# DSI_LCD.net
KiCad netlist of a schematic drawn in Altium Designer
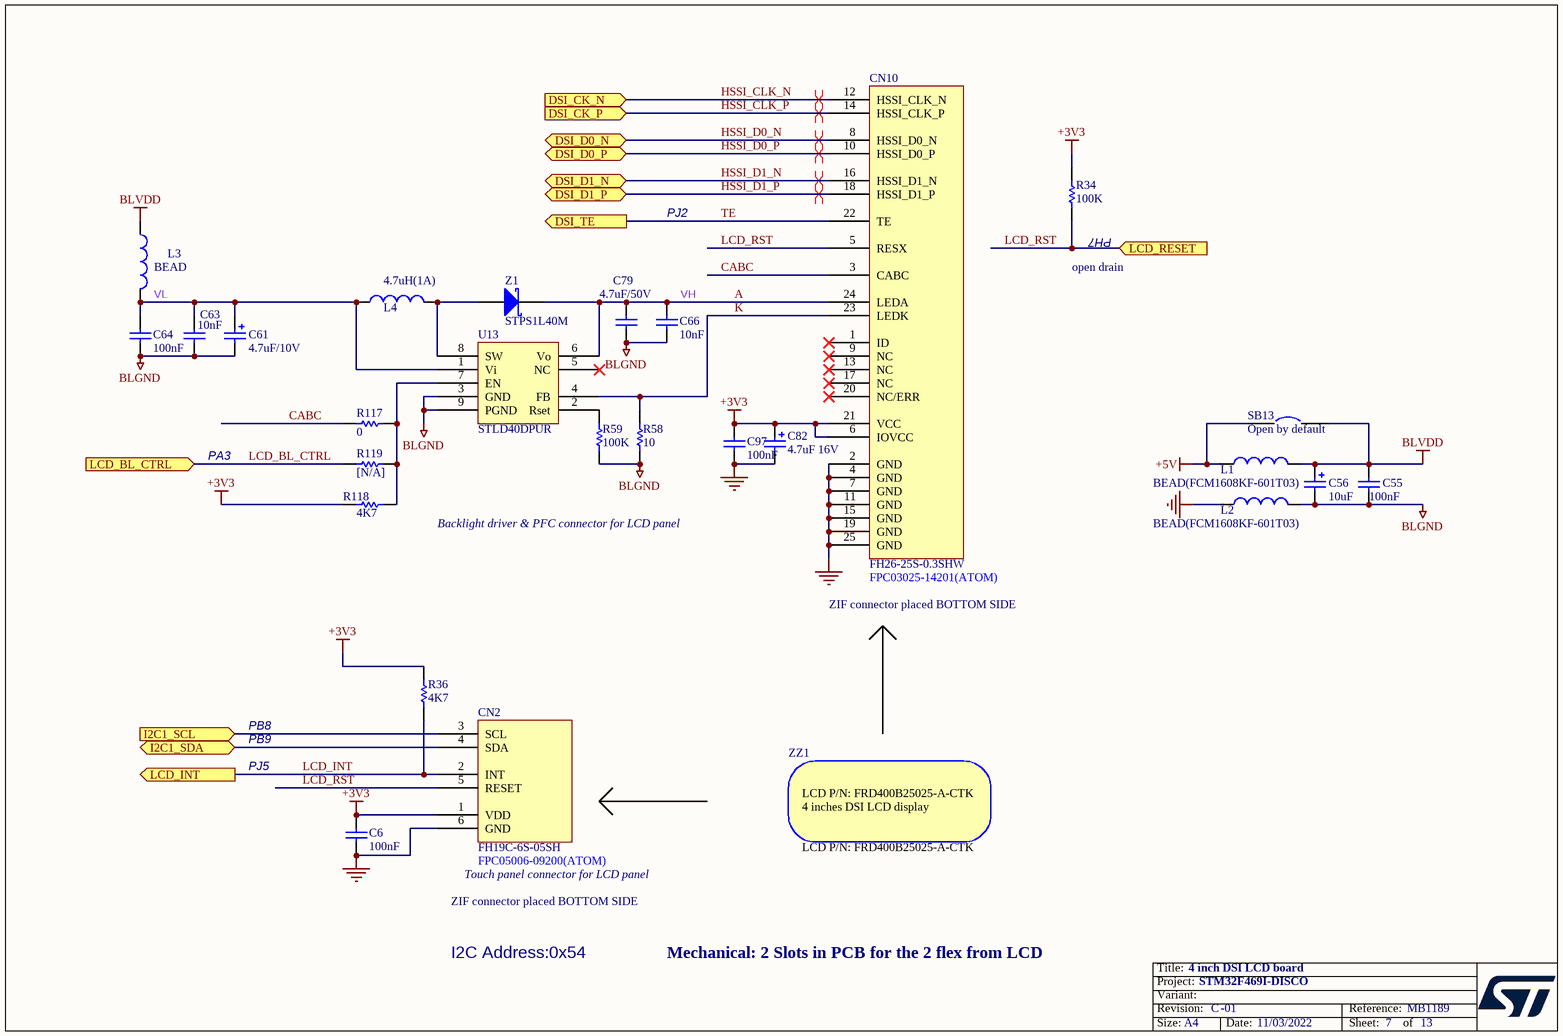
[diagram p0: DSI_LCD.SchDoc]

(export (version "E")
  (design (tool "Eeschema 10.0.6"))
  (components
    (comp (ref "C6")
      (value "100nF")
      (footprint "0402C")
      (description "Capacitor")
      (fields (field (name "PUBLISHER") "Altium Limited"))
      (libsource (lib "Miscellaneous Devices") (part "CAP"))
    )
    (comp (ref "C55")
      (value "100nF")
      (footprint "0402C")
      (description "Capacitor")
      (fields (field (name "PUBLISHER") "Altium Limited"))
      (libsource (lib "Miscellaneous Devices") (part "Cap"))
    )
    (comp (ref "C56")
      (value "10uF")
      (footprint "CPOL_TAJ-A_1206_H180")
      (description "Capacitor, Tantalum, 10uF, 16V, 10%, 3Ohms, pkg Type_A (3216 metric), T=1.6mm")
      (libsource (lib "MB1189") (part "Cap_TAJA106K016R"))
    )
    (comp (ref "C61")
      (value "4.7uF/10V")
      (footprint "1206C")
      (description "Polarized Capacitor (Radial)")
      (fields (field (name "PUBLISHER") "Altium Limited"))
      (libsource (lib "Miscellaneous Devices") (part "Cap Pol1"))
    )
    (comp (ref "C63")
      (value "10nF")
      (footprint "0603C")
      (description "Capacitor")
      (fields (field (name "PUBLISHER") "Altium Limited"))
      (libsource (lib "Miscellaneous Devices") (part "CAP"))
    )
    (comp (ref "C64")
      (value "100nF")
      (footprint "0402C")
      (description "Capacitor")
      (fields (field (name "PUBLISHER") "Altium Limited"))
      (libsource (lib "Miscellaneous Devices") (part "CAP"))
    )
    (comp (ref "C66")
      (value "10nF")
      (footprint "0603C")
      (description "Capacitor")
      (fields (field (name "PUBLISHER") "Altium Limited"))
      (libsource (lib "*") (part "CAP"))
    )
    (comp (ref "C79")
      (value "4.7uF/50V")
      (footprint "1206C")
      (description "Capacitor")
      (fields (field (name "PUBLISHER") "Altium Limited"))
      (libsource (lib "Miscellaneous Devices") (part "CAP"))
    )
    (comp (ref "C82")
      (value "4.7uF 16V")
      (footprint "CPOL_TAJ-A_1206_H180")
      (description "Capacitor, Tantalum, 4.7uF, 16V, 10%, 4ohms, pkg Type_A (3216 metric), T=1.6mm")
      (libsource (lib "MB1189") (part "Cap_TAJA475K016R"))
    )
    (comp (ref "C97")
      (value "100nF")
      (footprint "0402C")
      (description "Capacitor")
      (fields (field (name "PUBLISHER") "Altium Limited"))
      (libsource (lib "Miscellaneous Devices") (part "CAP"))
    )
    (comp (ref "CN2")
      (value "FH19C-6S-05SH")
      (footprint "FH19C-6S-0R5SH_FPC_CPT")
      (description "ZIF connector placed bottom side")
      (libsource (lib "MB1166") (part "FH19C-6S-05SH"))
    )
    (comp (ref "CN10")
      (value "FH26-25S-0.3SHW")
      (footprint "FPC25_FPC03025-1420")
      (description "ZIF connector placed bottom side")
      (libsource (lib "MB1166") (part "FH26-25S-0.3SHW"))
    )
    (comp (ref "L1")
      (value "BEAD(FCM1608KF-601T03)")
      (footprint "0603L")
      (description "Inductor")
      (fields (field (name "PUBLISHER") "Altium Limited"))
      (libsource (lib "Miscellaneous Devices") (part "Inductor"))
    )
    (comp (ref "L2")
      (value "BEAD(FCM1608KF-601T03)")
      (footprint "0603L")
      (description "Inductor")
      (fields (field (name "PUBLISHER") "Altium Limited"))
      (libsource (lib "Miscellaneous Devices") (part "Inductor"))
    )
    (comp (ref "L3")
      (value "BEAD")
      (footprint "0603L")
      (description "Inductor")
      (fields (field (name "PUBLISHER") "Altium Limited"))
      (libsource (lib "Miscellaneous Devices") (part "Inductor"))
    )
    (comp (ref "L4")
      (value "4.7uH(1A)")
      (footprint "1210L")
      (description "Inductor")
      (fields (field (name "PUBLISHER") "Altium Limited"))
      (libsource (lib "Miscellaneous Devices") (part "Inductor"))
    )
    (comp (ref "R34")
      (value "100K")
      (footprint "0402R")
      (description "Resistor")
      (fields (field (name "PUBLISHER") "Altium Limited"))
      (libsource (lib "Miscellaneous Devices") (part "Res1"))
    )
    (comp (ref "R36")
      (value "4K7")
      (footprint "0603R")
      (description "Resistor")
      (fields (field (name "PUBLISHER") "Altium Limited"))
      (libsource (lib "*") (part "Res1"))
    )
    (comp (ref "R58")
      (value "10")
      (footprint "0603R")
      (description "Resistor")
      (fields (field (name "PUBLISHER") "Altium Limited"))
      (libsource (lib "Miscellaneous Devices") (part "Res1"))
    )
    (comp (ref "R59")
      (value "100K")
      (footprint "0603R")
      (description "Resistor")
      (fields (field (name "PUBLISHER") "Altium Limited"))
      (libsource (lib "Miscellaneous Devices") (part "Res1"))
    )
    (comp (ref "R117")
      (value "0")
      (footprint "0603R")
      (description "Resistor")
      (fields (field (name "PUBLISHER") "Altium Limited"))
      (libsource (lib "Miscellaneous Devices") (part "Res1"))
    )
    (comp (ref "R118")
      (value "4K7")
      (footprint "0603R")
      (description "Resistor")
      (fields (field (name "PUBLISHER") "Altium Limited"))
      (libsource (lib "Miscellaneous Devices") (part "Res1"))
    )
    (comp (ref "R119")
      (value "[N/A]")
      (footprint "0603R")
      (description "Resistor")
      (fields (field (name "PUBLISHER") "Altium Limited"))
      (libsource (lib "Miscellaneous Devices") (part "Res1"))
    )
    (comp (ref "SB13")
      (value "Open by default")
      (footprint "SB_0603")
      (description "Circuit Breaker")
      (fields (field (name "PUBLISHER") "Altium Limited"))
      (libsource (lib "Miscellaneous Devices") (part "Circuit Breaker"))
    )
    (comp (ref "U13")
      (value "STLD40DPUR")
      (footprint "SON8_0R65_3X3")
      (libsource (lib "3.2LCD_daughterboard") (part "STLD40DPMR"))
    )
    (comp (ref "Z1")
      (value "STPS1L40M")
      (footprint "DO-216AA")
      (description "Schottky Diode")
      (fields (field (name "PUBLISHER") "Altium Limited"))
      (libsource (lib "Miscellaneous Devices") (part "D Schottky"))
    )
    (comp (ref "ZZ1")
      (value "LCD P/N: FRD400B25025-A-CTK")
      (footprint "toto")
      (description "4 inches DSI LCD with touch screen")
      (libsource (lib "MB1189") (part "LCD"))
    )
  )
  (nets
    (net (code "1") (name "+3V3") (class "Default")
      (node (ref "C6") (pin "2") (pinfunction "2_2") (pintype "passive"))
      (node (ref "C82") (pin "1") (pinfunction "1_1") (pintype "passive"))
      (node (ref "C97") (pin "2") (pinfunction "2_2") (pintype "passive"))
      (node (ref "CN10") (pin "21") (pinfunction "VCC_21") (pintype "passive"))
      (node (ref "CN10") (pin "6") (pinfunction "IOVCC_6") (pintype "passive"))
      (node (ref "CN2") (pin "1") (pinfunction "VDD_1") (pintype "passive"))
      (node (ref "R118") (pin "2") (pinfunction "2_2") (pintype "passive"))
      (node (ref "R34") (pin "1") (pinfunction "1_1") (pintype "passive"))
      (node (ref "R36") (pin "1") (pinfunction "1_1") (pintype "passive"))
    )
    (net (code "2") (name "+5V") (class "Default")
      (node (ref "L1") (pin "1") (pinfunction "1_1") (pintype "passive"))
      (node (ref "SB13") (pin "1") (pinfunction "1_1") (pintype "passive"))
    )
    (net (code "3") (name "/A") (class "Default")
      (node (ref "C66") (pin "2") (pinfunction "2_2") (pintype "passive"))
      (node (ref "C79") (pin "1") (pinfunction "1_1") (pintype "passive"))
      (node (ref "CN10") (pin "24") (pinfunction "LEDA_24") (pintype "passive"))
      (node (ref "U13") (pin "6") (pinfunction "Vo_6") (pintype "passive"))
      (node (ref "Z1") (pin "2") (pinfunction "K_2") (pintype "passive"))
    )
    (net (code "4") (name "/CABC") (class "Default")
      (node (ref "CN10") (pin "3") (pinfunction "CABC_3") (pintype "passive"))
      (node (ref "R117") (pin "2") (pinfunction "2_2") (pintype "passive"))
    )
    (net (code "5") (name "/HSSI_CLK_N") (class "Default")
      (node (ref "CN10") (pin "12") (pinfunction "HSSI_CLK_N_12") (pintype "passive"))
    )
    (net (code "6") (name "/HSSI_CLK_P") (class "Default")
      (node (ref "CN10") (pin "14") (pinfunction "HSSI_CLK_P_14") (pintype "passive"))
    )
    (net (code "7") (name "/HSSI_D0_N") (class "Default")
      (node (ref "CN10") (pin "8") (pinfunction "HSSI_D0_N_8") (pintype "passive"))
    )
    (net (code "8") (name "/HSSI_D0_P") (class "Default")
      (node (ref "CN10") (pin "10") (pinfunction "HSSI_D0_P_10") (pintype "passive"))
    )
    (net (code "9") (name "/HSSI_D1_N") (class "Default")
      (node (ref "CN10") (pin "16") (pinfunction "HSSI_D1_N_16") (pintype "passive"))
    )
    (net (code "10") (name "/HSSI_D1_P") (class "Default")
      (node (ref "CN10") (pin "18") (pinfunction "HSSI_D1_P_18") (pintype "passive"))
    )
    (net (code "11") (name "/I2C1_SCL") (class "Default")
      (node (ref "CN2") (pin "3") (pinfunction "SCL_3") (pintype "passive"))
    )
    (net (code "12") (name "/I2C1_SDA") (class "Default")
      (node (ref "CN2") (pin "4") (pinfunction "SDA_4") (pintype "passive"))
    )
    (net (code "13") (name "/K") (class "Default")
      (node (ref "CN10") (pin "23") (pinfunction "LEDK_23") (pintype "passive"))
      (node (ref "R58") (pin "2") (pinfunction "2_2") (pintype "passive"))
      (node (ref "U13") (pin "4") (pinfunction "FB_4") (pintype "passive"))
    )
    (net (code "14") (name "/LCD_BL_CTRL") (class "Default")
      (node (ref "R119") (pin "2") (pinfunction "2_2") (pintype "passive"))
    )
    (net (code "15") (name "/LCD_INT") (class "Default")
      (node (ref "CN2") (pin "2") (pinfunction "INT_2") (pintype "passive"))
      (node (ref "R36") (pin "2") (pinfunction "2_2") (pintype "passive"))
    )
    (net (code "16") (name "/LCD_RST") (class "Default")
      (node (ref "CN10") (pin "5") (pinfunction "RESX_5") (pintype "passive"))
      (node (ref "CN2") (pin "5") (pinfunction "RESET_5") (pintype "passive"))
      (node (ref "R34") (pin "2") (pinfunction "2_2") (pintype "passive"))
    )
    (net (code "17") (name "/TE") (class "Default")
      (node (ref "CN10") (pin "22") (pinfunction "TE_22") (pintype "passive"))
    )
    (net (code "18") (name "/VL") (class "Default")
      (node (ref "C61") (pin "1") (pinfunction "1_1") (pintype "passive"))
      (node (ref "C63") (pin "2") (pinfunction "2_2") (pintype "passive"))
      (node (ref "C64") (pin "2") (pinfunction "2_2") (pintype "passive"))
      (node (ref "L3") (pin "2") (pinfunction "2_2") (pintype "passive"))
      (node (ref "L4") (pin "1") (pinfunction "1_1") (pintype "passive"))
      (node (ref "U13") (pin "1") (pinfunction "Vi_1") (pintype "passive"))
    )
    (net (code "19") (name "BLGND") (class "Default")
      (node (ref "C55") (pin "2") (pinfunction "2_2") (pintype "passive"))
      (node (ref "C56") (pin "2") (pinfunction "2_2") (pintype "passive"))
      (node (ref "C61") (pin "2") (pinfunction "2_2") (pintype "passive"))
      (node (ref "C63") (pin "1") (pinfunction "1_1") (pintype "passive"))
      (node (ref "C64") (pin "1") (pinfunction "1_1") (pintype "passive"))
      (node (ref "C66") (pin "1") (pinfunction "1_1") (pintype "passive"))
      (node (ref "C79") (pin "2") (pinfunction "2_2") (pintype "passive"))
      (node (ref "L2") (pin "2") (pinfunction "2_2") (pintype "passive"))
      (node (ref "R58") (pin "1") (pinfunction "1_1") (pintype "passive"))
      (node (ref "R59") (pin "2") (pinfunction "2_2") (pintype "passive"))
      (node (ref "U13") (pin "3") (pinfunction "GND_3") (pintype "passive"))
      (node (ref "U13") (pin "9") (pinfunction "PGND_9") (pintype "passive"))
    )
    (net (code "20") (name "BLVDD") (class "Default")
      (node (ref "C55") (pin "1") (pinfunction "1_1") (pintype "passive"))
      (node (ref "C56") (pin "1") (pinfunction "1_1") (pintype "passive"))
      (node (ref "L1") (pin "2") (pinfunction "2_2") (pintype "passive"))
      (node (ref "L3") (pin "1") (pinfunction "1_1") (pintype "passive"))
      (node (ref "SB13") (pin "2") (pinfunction "2_2") (pintype "passive"))
    )
    (net (code "21") (name "GND") (class "Default")
      (node (ref "C6") (pin "1") (pinfunction "1_1") (pintype "passive"))
      (node (ref "C82") (pin "2") (pinfunction "2_2") (pintype "passive"))
      (node (ref "C97") (pin "1") (pinfunction "1_1") (pintype "passive"))
      (node (ref "CN10") (pin "11") (pinfunction "GND_11") (pintype "passive"))
      (node (ref "CN10") (pin "15") (pinfunction "GND_15") (pintype "passive"))
      (node (ref "CN10") (pin "19") (pinfunction "GND_19") (pintype "passive"))
      (node (ref "CN10") (pin "2") (pinfunction "GND_2") (pintype "passive"))
      (node (ref "CN10") (pin "25") (pinfunction "GND_25") (pintype "passive"))
      (node (ref "CN10") (pin "4") (pinfunction "GND_4") (pintype "passive"))
      (node (ref "CN10") (pin "7") (pinfunction "GND_7") (pintype "passive"))
      (node (ref "CN2") (pin "6") (pinfunction "GND_6") (pintype "passive"))
      (node (ref "L2") (pin "1") (pinfunction "1_1") (pintype "passive"))
    )
    (net (code "22") (name "Net-(U13-EN)") (class "Default")
      (node (ref "R117") (pin "1") (pinfunction "1_1") (pintype "passive"))
      (node (ref "R118") (pin "1") (pinfunction "1_1") (pintype "passive"))
      (node (ref "R119") (pin "1") (pinfunction "1_1") (pintype "passive"))
      (node (ref "U13") (pin "7") (pinfunction "EN_7") (pintype "passive"))
    )
    (net (code "23") (name "Net-(U13-Rset)") (class "Default")
      (node (ref "R59") (pin "1") (pinfunction "1_1") (pintype "passive"))
      (node (ref "U13") (pin "2") (pinfunction "Rset_2") (pintype "passive"))
    )
    (net (code "24") (name "Net-(U13-SW)") (class "Default")
      (node (ref "L4") (pin "2") (pinfunction "2_2") (pintype "passive"))
      (node (ref "U13") (pin "8") (pinfunction "SW_8") (pintype "passive"))
      (node (ref "Z1") (pin "1") (pinfunction "A_1") (pintype "passive"))
    )
    (net (code "25") (name "unconnected-(CN10-ID-Pad1)") (class "Default")
      (node (ref "CN10") (pin "1") (pinfunction "ID_1") (pintype "passive+no_connect"))
    )
    (net (code "26") (name "unconnected-(CN10-NC-Pad9)") (class "Default")
      (node (ref "CN10") (pin "9") (pinfunction "NC_9") (pintype "passive+no_connect"))
    )
    (net (code "27") (name "unconnected-(CN10-NC-Pad13)") (class "Default")
      (node (ref "CN10") (pin "13") (pinfunction "NC_13") (pintype "passive+no_connect"))
    )
    (net (code "28") (name "unconnected-(CN10-NC-Pad17)") (class "Default")
      (node (ref "CN10") (pin "17") (pinfunction "NC_17") (pintype "passive+no_connect"))
    )
    (net (code "29") (name "unconnected-(CN10-NC{slash}ERR-Pad20)") (class "Default")
      (node (ref "CN10") (pin "20") (pinfunction "NC/ERR_20") (pintype "passive+no_connect"))
    )
    (net (code "30") (name "unconnected-(U13-NC-Pad5)") (class "Default")
      (node (ref "U13") (pin "5") (pinfunction "NC_5") (pintype "passive+no_connect"))
    )
  )
)
